# LB_i14_BENDSENSOR-v03_rev2.net
KiCad netlist of a schematic drawn in EAGLE
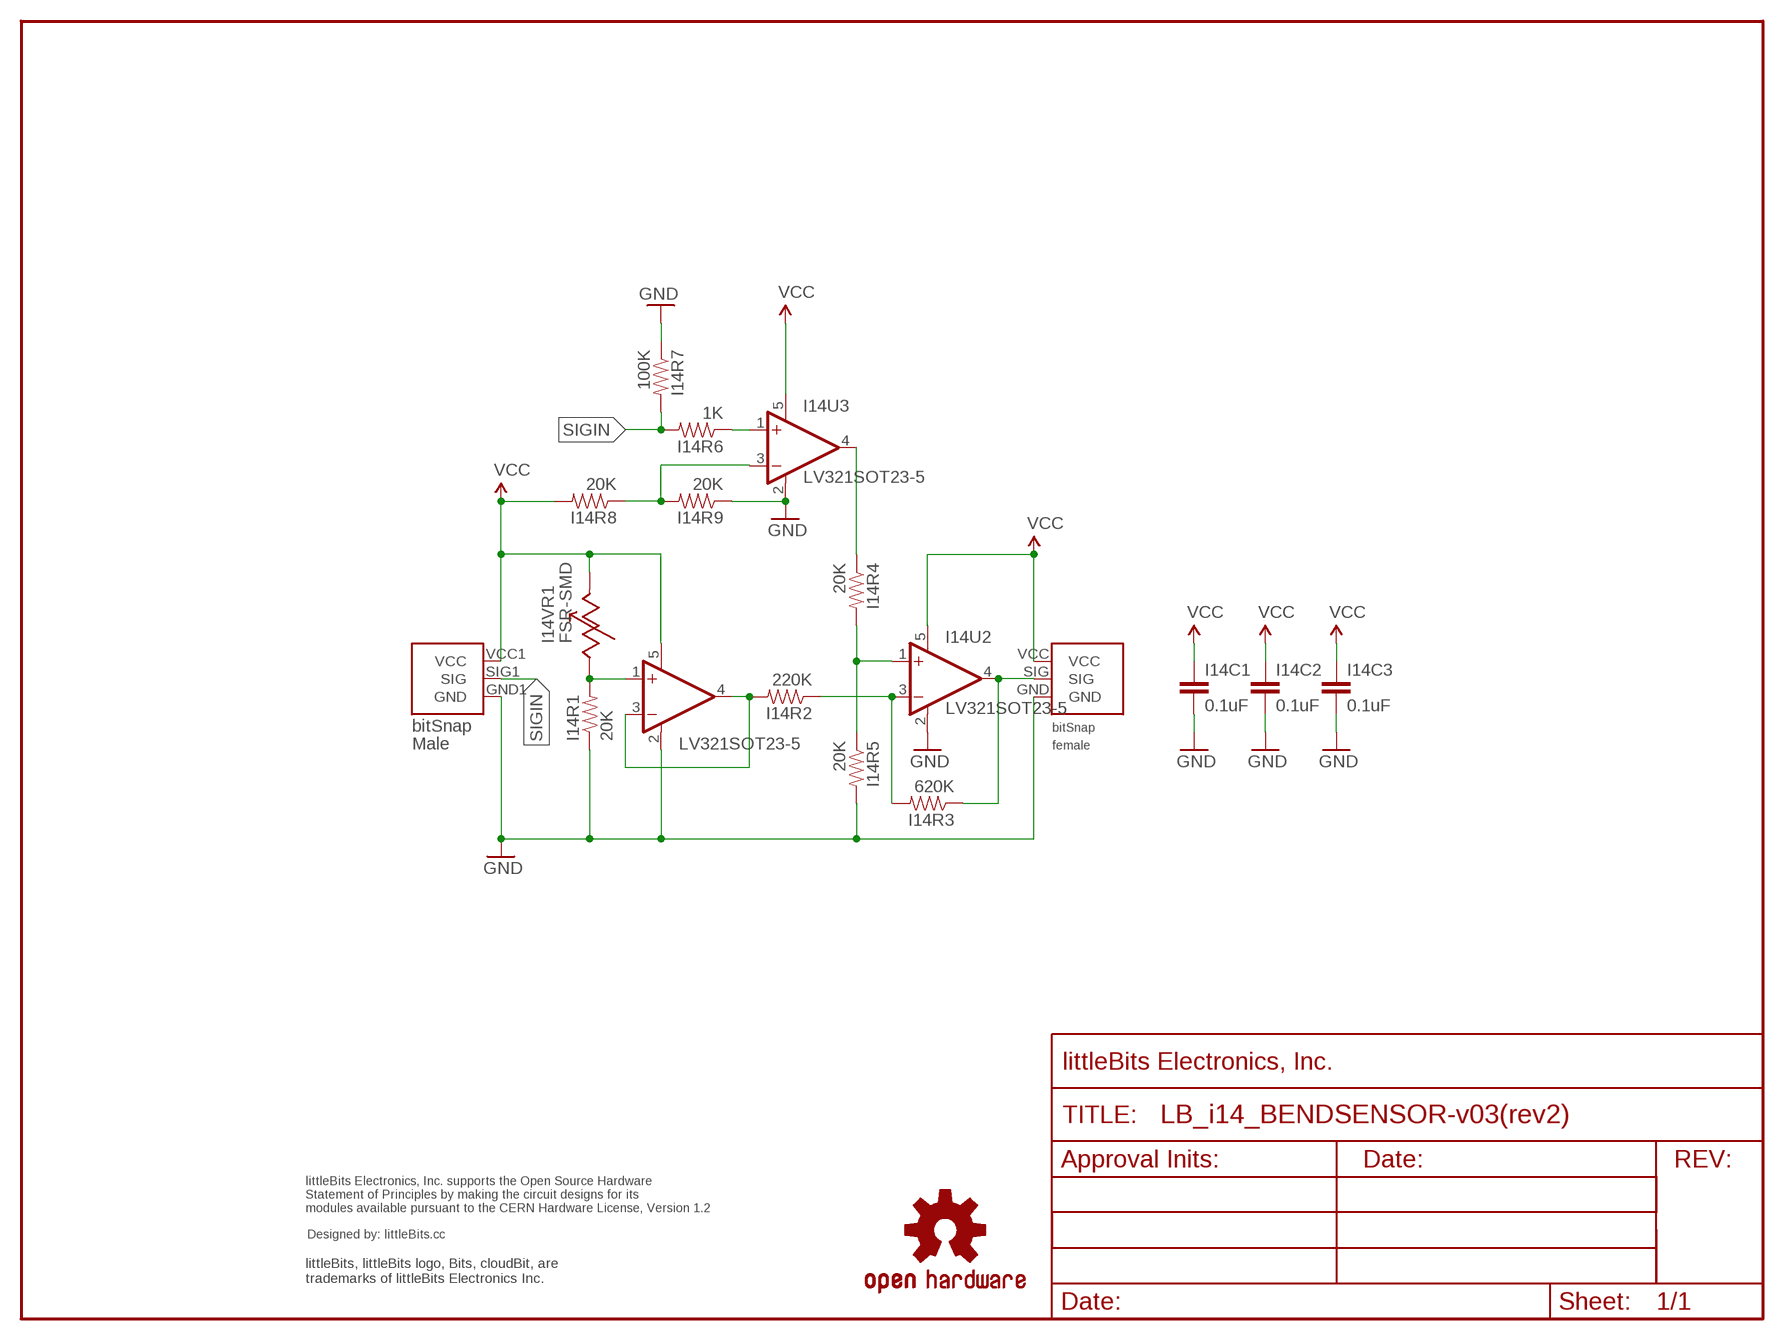
[diagram p0: schematic, sheet 1]

(export (version "E")
  (design (tool "Eeschema 10.0.6"))
  (components
    (comp (ref "I14BSM")
      (value "BITSNAP_V03_MALE")
      (footprint "eagle-import:BITSNAP_V03_MALE")
      (libsource (lib "eagle-import") (part "BITSNAP_V03_MALE"))
    )
    (comp (ref "I14C1")
      (value "0.1uF")
      (footprint "eagle-import:0603-CAP")
      (libsource (lib "eagle-import") (part "CAP0603-CAP"))
    )
    (comp (ref "I14C2")
      (value "0.1uF")
      (footprint "eagle-import:0603-CAP")
      (libsource (lib "eagle-import") (part "CAP0603-CAP"))
    )
    (comp (ref "I14C3")
      (value "0.1uF")
      (footprint "eagle-import:0603-CAP")
      (libsource (lib "eagle-import") (part "CAP0603-CAP"))
    )
    (comp (ref "I14R1")
      (value "20K")
      (footprint "eagle-import:0603-RES")
      (libsource (lib "eagle-import") (part "RESISTOR0603-RES"))
    )
    (comp (ref "I14R2")
      (value "220K")
      (footprint "eagle-import:0603-RES")
      (libsource (lib "eagle-import") (part "RESISTOR0603-RES"))
    )
    (comp (ref "I14R3")
      (value "620K")
      (footprint "eagle-import:0603-RES")
      (libsource (lib "eagle-import") (part "RESISTOR0603-RES"))
    )
    (comp (ref "I14R4")
      (value "20K")
      (footprint "eagle-import:0603-RES")
      (libsource (lib "eagle-import") (part "RESISTOR0603-RES"))
    )
    (comp (ref "I14R5")
      (value "20K")
      (footprint "eagle-import:0603-RES")
      (libsource (lib "eagle-import") (part "RESISTOR0603-RES"))
    )
    (comp (ref "I14R6")
      (value "1K")
      (footprint "eagle-import:0603-RES")
      (libsource (lib "eagle-import") (part "RESISTOR0603-RES"))
    )
    (comp (ref "I14R7")
      (value "100K")
      (footprint "eagle-import:0603-RES")
      (libsource (lib "eagle-import") (part "RESISTOR0603-RES"))
    )
    (comp (ref "I14R8")
      (value "20K")
      (footprint "eagle-import:0603-RES")
      (libsource (lib "eagle-import") (part "RESISTOR0603-RES"))
    )
    (comp (ref "I14R9")
      (value "20K")
      (footprint "eagle-import:0603-RES")
      (libsource (lib "eagle-import") (part "RESISTOR0603-RES"))
    )
    (comp (ref "I14U1")
      (value "LV321SOT23-5")
      (footprint "eagle-import:SOT23-5")
      (libsource (lib "eagle-import") (part "LV321SOT23-5"))
    )
    (comp (ref "I14U2")
      (value "LV321SOT23-5")
      (footprint "eagle-import:SOT23-5")
      (libsource (lib "eagle-import") (part "LV321SOT23-5"))
    )
    (comp (ref "I14U3")
      (value "LV321SOT23-5")
      (footprint "eagle-import:SOT23-5")
      (libsource (lib "eagle-import") (part "LV321SOT23-5"))
    )
    (comp (ref "I14VR1")
      (value "FSR-SMD")
      (footprint "eagle-import:FSR-SMD")
      (libsource (lib "eagle-import") (part "FSR-SMD"))
    )
    (comp (ref "U$1")
      (value "OSHW-LOGOL")
      (footprint "eagle-import:OSHW-LOGO-L")
      (libsource (lib "eagle-import") (part "OSHW-LOGOL"))
    )
    (comp (ref "U$2")
      (value "FRAME-LETTER-OHWOHW")
      (footprint "eagle-import:FABDWG01-OHW")
      (libsource (lib "eagle-import") (part "FRAME-LETTER-OHWOHW"))
    )
    (comp (ref "U$3")
      (value "OSHWCREDIT")
      (footprint "eagle-import:OSHWCREDIT")
      (libsource (lib "eagle-import") (part "OSHWCREDIT"))
    )
    (comp (ref "U$4I14BSF")
      (value "BITSNAP_V03_FEMALE")
      (footprint "eagle-import:BITSNAP_V03_FEMALE")
      (libsource (lib "eagle-import") (part "BITSNAP_V03_FEMALE"))
    )
  )
  (nets
    (net (code "1") (name "GND") (class "Default")
      (node (ref "I14BSM") (pin "GND1") (pinfunction "GND_GND1") (pintype "bidirectional"))
      (node (ref "I14C1") (pin "2") (pinfunction "2_2") (pintype "passive"))
      (node (ref "I14C2") (pin "2") (pinfunction "2_2") (pintype "passive"))
      (node (ref "I14C3") (pin "2") (pinfunction "2_2") (pintype "passive"))
      (node (ref "I14R1") (pin "1") (pinfunction "1_1") (pintype "passive"))
      (node (ref "I14R5") (pin "2") (pinfunction "2_2") (pintype "passive"))
      (node (ref "I14R7") (pin "1") (pinfunction "1_1") (pintype "passive"))
      (node (ref "I14R9") (pin "1") (pinfunction "1_1") (pintype "passive"))
      (node (ref "I14U1") (pin "2") (pinfunction "V-_2") (pintype "power_in"))
      (node (ref "I14U2") (pin "2") (pinfunction "V-_2") (pintype "power_in"))
      (node (ref "I14U3") (pin "2") (pinfunction "V-_2") (pintype "power_in"))
      (node (ref "U$4I14BSF") (pin "GND") (pinfunction "GND_GND") (pintype "bidirectional"))
    )
    (net (code "2") (name "Net-(I14U1-+IN)") (class "Default")
      (node (ref "I14R1") (pin "2") (pinfunction "2_2") (pintype "passive"))
      (node (ref "I14U1") (pin "1") (pinfunction "+IN_1") (pintype "input"))
      (node (ref "I14VR1") (pin "2") (pinfunction "A_2") (pintype "passive"))
    )
    (net (code "3") (name "Net-(I14U1--IN)") (class "Default")
      (node (ref "I14R2") (pin "2") (pinfunction "2_2") (pintype "passive"))
      (node (ref "I14U1") (pin "3") (pinfunction "-IN_3") (pintype "input"))
      (node (ref "I14U1") (pin "4") (pinfunction "OUT_4") (pintype "output"))
    )
    (net (code "4") (name "Net-(I14U2-+IN)") (class "Default")
      (node (ref "I14R4") (pin "2") (pinfunction "2_2") (pintype "passive"))
      (node (ref "I14R5") (pin "1") (pinfunction "1_1") (pintype "passive"))
      (node (ref "I14U2") (pin "1") (pinfunction "+IN_1") (pintype "input"))
    )
    (net (code "5") (name "Net-(I14U2--IN)") (class "Default")
      (node (ref "I14R2") (pin "1") (pinfunction "1_1") (pintype "passive"))
      (node (ref "I14R3") (pin "2") (pinfunction "2_2") (pintype "passive"))
      (node (ref "I14U2") (pin "3") (pinfunction "-IN_3") (pintype "input"))
    )
    (net (code "6") (name "Net-(I14U2-OUT)") (class "Default")
      (node (ref "I14R3") (pin "1") (pinfunction "1_1") (pintype "passive"))
      (node (ref "I14U2") (pin "4") (pinfunction "OUT_4") (pintype "output"))
      (node (ref "U$4I14BSF") (pin "SIG") (pinfunction "SIG_SIG") (pintype "bidirectional"))
    )
    (net (code "7") (name "Net-(I14U3-+IN)") (class "Default")
      (node (ref "I14R6") (pin "1") (pinfunction "1_1") (pintype "passive"))
      (node (ref "I14U3") (pin "1") (pinfunction "+IN_1") (pintype "input"))
    )
    (net (code "8") (name "Net-(I14U3--IN)") (class "Default")
      (node (ref "I14R8") (pin "1") (pinfunction "1_1") (pintype "passive"))
      (node (ref "I14R9") (pin "2") (pinfunction "2_2") (pintype "passive"))
      (node (ref "I14U3") (pin "3") (pinfunction "-IN_3") (pintype "input"))
    )
    (net (code "9") (name "Net-(I14U3-OUT)") (class "Default")
      (node (ref "I14R4") (pin "1") (pinfunction "1_1") (pintype "passive"))
      (node (ref "I14U3") (pin "4") (pinfunction "OUT_4") (pintype "output"))
    )
    (net (code "10") (name "SIGIN") (class "Default")
      (node (ref "I14BSM") (pin "SIG1") (pinfunction "SIG_SIG1") (pintype "bidirectional"))
      (node (ref "I14R6") (pin "2") (pinfunction "2_2") (pintype "passive"))
      (node (ref "I14R7") (pin "2") (pinfunction "2_2") (pintype "passive"))
    )
    (net (code "11") (name "VCC") (class "Default")
      (node (ref "I14BSM") (pin "VCC1") (pinfunction "VCC_VCC1") (pintype "bidirectional"))
      (node (ref "I14C1") (pin "1") (pinfunction "1_1") (pintype "passive"))
      (node (ref "I14C2") (pin "1") (pinfunction "1_1") (pintype "passive"))
      (node (ref "I14C3") (pin "1") (pinfunction "1_1") (pintype "passive"))
      (node (ref "I14R8") (pin "2") (pinfunction "2_2") (pintype "passive"))
      (node (ref "I14U1") (pin "5") (pinfunction "V+_5") (pintype "power_in"))
      (node (ref "I14U2") (pin "5") (pinfunction "V+_5") (pintype "power_in"))
      (node (ref "I14U3") (pin "5") (pinfunction "V+_5") (pintype "power_in"))
      (node (ref "I14VR1") (pin "1") (pinfunction "1_1") (pintype "passive"))
      (node (ref "U$4I14BSF") (pin "VCC") (pinfunction "VCC_VCC") (pintype "bidirectional"))
    )
  )
)
